# v2_1.net
KiCad netlist of a schematic drawn in EAGLE
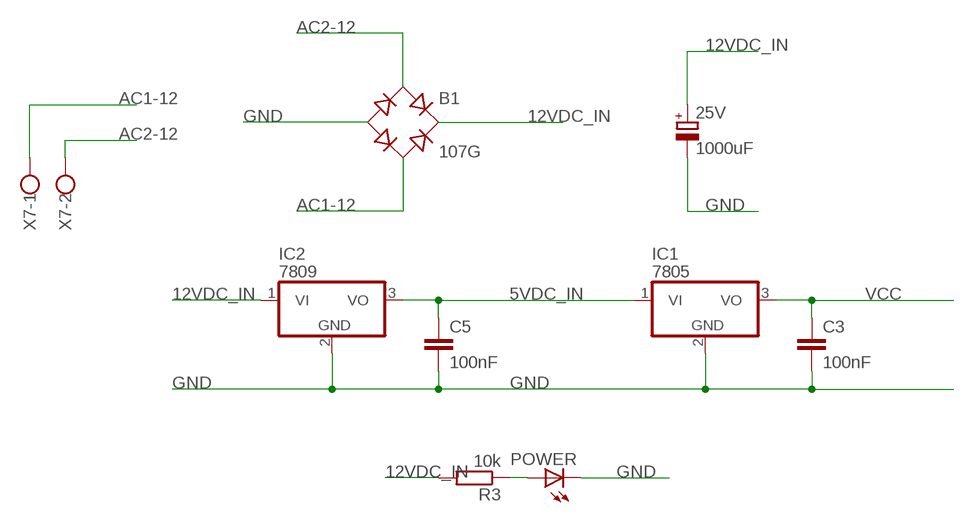
[diagram p0: schematic, sheet 1]
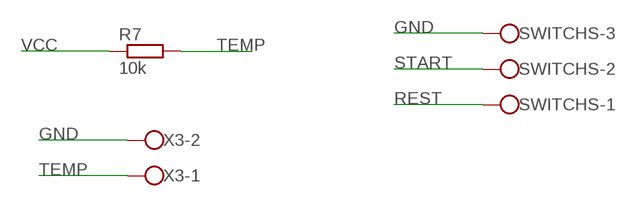
[diagram p1: schematic, sheet 2]
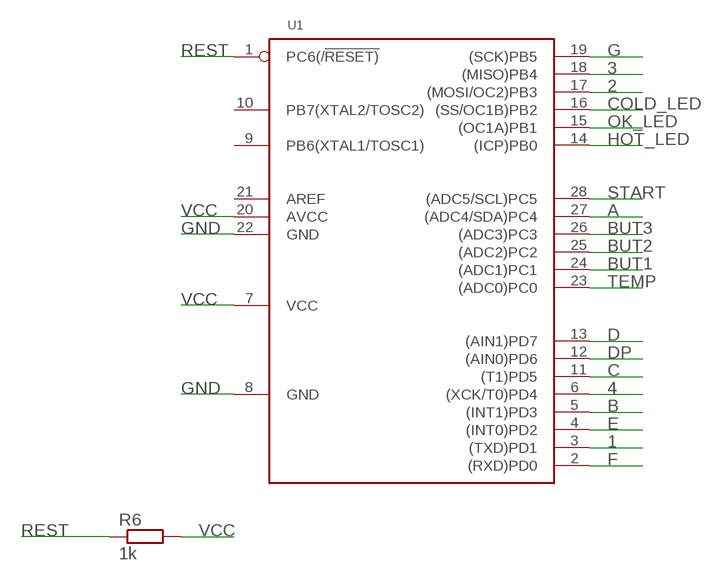
[diagram p2: schematic, sheet 3]
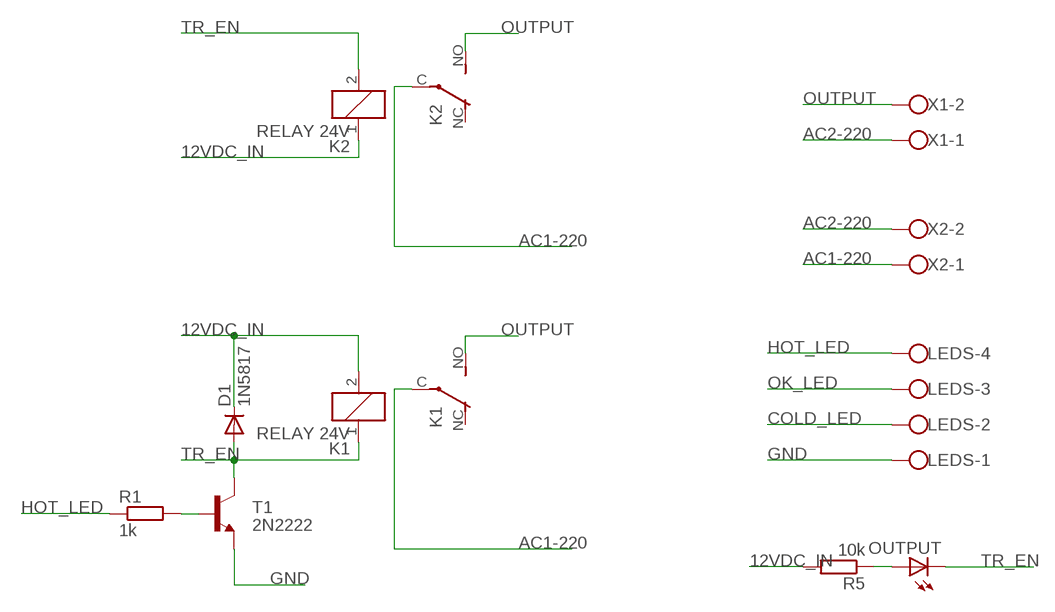
[diagram p3: schematic, sheet 4]

(export (version "E")
  (design (tool "Eeschema 10.0.6"))
  (components
    (comp (ref "25V")
      (value "1000uF")
      (footprint "eagle-import:E3,5-8")
      (libsource (lib "eagle-import") (part "CPOL-EUE3.5-8"))
    )
    (comp (ref "B1")
      (value "107G")
      (footprint "eagle-import:DB")
      (libsource (lib "eagle-import") (part "DB?GDB101"))
    )
    (comp (ref "C3")
      (value "100nF")
      (footprint "eagle-import:C050-025X075")
      (libsource (lib "eagle-import") (part "C-EU050-025X075"))
    )
    (comp (ref "C5")
      (value "100nF")
      (footprint "eagle-import:C050-025X075")
      (libsource (lib "eagle-import") (part "C-EU050-025X075"))
    )
    (comp (ref "IC1")
      (value "7805")
      (footprint "eagle-import:TO220V")
      (libsource (lib "eagle-import") (part "78TV12"))
    )
    (comp (ref "IC2")
      (value "7809")
      (footprint "eagle-import:TO220V")
      (libsource (lib "eagle-import") (part "78TV12"))
    )
    (comp (ref "POWER")
      (value "LED5MM")
      (footprint "eagle-import:LED5MM")
      (libsource (lib "eagle-import") (part "LED5MM"))
    )
    (comp (ref "R3")
      (value "10k")
      (footprint "eagle-import:0207_10")
      (libsource (lib "eagle-import") (part "R-EU_0207/10"))
    )
    (comp (ref "X7")
      (value "W237-102")
      (footprint "eagle-import:W237-102")
      (libsource (lib "eagle-import") (part "W237-102"))
    )
    (comp (ref "D1")
      (value "1N5817")
      (footprint "eagle-import:DO41-10")
      (libsource (lib "eagle-import") (part "1N4004"))
    )
    (comp (ref "K1")
      (value "RELAY 24V")
      (footprint "eagle-import:JS-M")
      (fields (field (name "MF") "FARNELL") (field (name "MPN") "JSM1-12V-5"))
      (libsource (lib "eagle-import") (part "JS-M1-12V-5"))
    )
    (comp (ref "K2")
      (value "RELAY 24V")
      (footprint "eagle-import:JS-M")
      (fields (field (name "MF") "FARNELL") (field (name "MPN") "JSM1-12V-5"))
      (libsource (lib "eagle-import") (part "JS-M1-12V-5"))
    )
    (comp (ref "LEDS")
      (value "W237-4")
      (footprint "eagle-import:W237-4")
      (libsource (lib "eagle-import") (part "W237-4"))
    )
    (comp (ref "OUTPUT")
      (value "LED5MM")
      (footprint "eagle-import:LED5MM")
      (libsource (lib "eagle-import") (part "LED5MM"))
    )
    (comp (ref "R1")
      (value "1k")
      (footprint "eagle-import:0207_10")
      (libsource (lib "eagle-import") (part "R-EU_0207/10"))
    )
    (comp (ref "R5")
      (value "10k")
      (footprint "eagle-import:0207_10")
      (libsource (lib "eagle-import") (part "R-EU_0207/10"))
    )
    (comp (ref "T1")
      (value "2N2222")
      (footprint "eagle-import:TO92-EBC-OVAL")
      (libsource (lib "eagle-import") (part "2N2222"))
    )
    (comp (ref "X1")
      (value "W237-102")
      (footprint "eagle-import:W237-102")
      (libsource (lib "eagle-import") (part "W237-102"))
    )
    (comp (ref "X2")
      (value "W237-102")
      (footprint "eagle-import:W237-102")
      (libsource (lib "eagle-import") (part "W237-102"))
    )
    (comp (ref "R6")
      (value "1k")
      (footprint "eagle-import:0207_10")
      (libsource (lib "eagle-import") (part "R-EU_0207/10"))
    )
    (comp (ref "U1")
      (value "MCU-ATMEGA328P-PU(DIP28)")
      (footprint "eagle-import:DIP28-2.54-34.7X7.62MM")
      (fields (field (name "MPN") "ATMEGA328P-PU"))
      (libsource (lib "eagle-import") (part "MCU-ATMEGA328P-PU(DIP28)"))
    )
    (comp (ref "R7")
      (value "10k")
      (footprint "eagle-import:0207_10")
      (libsource (lib "eagle-import") (part "R-EU_0207/10"))
    )
    (comp (ref "SWITCHS")
      (value "W237-103")
      (footprint "eagle-import:W237-103")
      (libsource (lib "eagle-import") (part "W237-103"))
    )
    (comp (ref "X3")
      (value "W237-102")
      (footprint "eagle-import:W237-102")
      (libsource (lib "eagle-import") (part "W237-102"))
    )
  )
  (nets
    (net (code "1") (name "1") (class "Default")
      (node (ref "U1") (pin "3") (pinfunction "(TXD)PD1_3") (pintype "bidirectional"))
    )
    (net (code "2") (name "2") (class "Default")
      (node (ref "U1") (pin "17") (pinfunction "(MOSI/OC2)PB3_17") (pintype "bidirectional"))
    )
    (net (code "3") (name "3") (class "Default")
      (node (ref "U1") (pin "18") (pinfunction "(MISO)PB4_18") (pintype "bidirectional"))
    )
    (net (code "4") (name "4") (class "Default")
      (node (ref "U1") (pin "6") (pinfunction "(XCK/T0)PD4_6") (pintype "bidirectional"))
    )
    (net (code "5") (name "5VDC_IN") (class "Default")
      (node (ref "C5") (pin "1") (pinfunction "1_1") (pintype "passive"))
      (node (ref "IC1") (pin "1") (pinfunction "VI_1") (pintype "input"))
      (node (ref "IC2") (pin "3") (pinfunction "VO_3") (pintype "passive"))
    )
    (net (code "6") (name "12VDC_IN") (class "Default")
      (node (ref "25V") (pin "+") (pinfunction "+_+") (pintype "passive"))
      (node (ref "B1") (pin "+") (pinfunction "+_+") (pintype "passive"))
      (node (ref "D1") (pin "C") (pinfunction "C_C") (pintype "passive"))
      (node (ref "IC2") (pin "1") (pinfunction "VI_1") (pintype "input"))
      (node (ref "K1") (pin "2") (pinfunction "2_2") (pintype "passive"))
      (node (ref "K2") (pin "1") (pinfunction "1_1") (pintype "passive"))
      (node (ref "R3") (pin "2") (pinfunction "2_2") (pintype "passive"))
      (node (ref "R5") (pin "2") (pinfunction "2_2") (pintype "passive"))
    )
    (net (code "7") (name "A") (class "Default")
      (node (ref "U1") (pin "27") (pinfunction "(ADC4/SDA)PC4_27") (pintype "bidirectional"))
    )
    (net (code "8") (name "AC1-12") (class "Default")
      (node (ref "B1") (pin "AC2") (pinfunction "AC2_AC2") (pintype "passive"))
      (node (ref "X7") (pin "1") (pinfunction "KL_1") (pintype "passive"))
    )
    (net (code "9") (name "AC1-220") (class "Default")
      (node (ref "K1") (pin "C") (pinfunction "P_C") (pintype "passive"))
      (node (ref "K2") (pin "C") (pinfunction "P_C") (pintype "passive"))
      (node (ref "X2") (pin "1") (pinfunction "KL_1") (pintype "passive"))
    )
    (net (code "10") (name "AC2-12") (class "Default")
      (node (ref "B1") (pin "AC1") (pinfunction "AC1_AC1") (pintype "passive"))
      (node (ref "X7") (pin "2") (pinfunction "KL_2") (pintype "passive"))
    )
    (net (code "11") (name "AC2-220") (class "Default")
      (node (ref "X1") (pin "1") (pinfunction "KL_1") (pintype "passive"))
      (node (ref "X2") (pin "2") (pinfunction "KL_2") (pintype "passive"))
    )
    (net (code "12") (name "B") (class "Default")
      (node (ref "U1") (pin "5") (pinfunction "(INT1)PD3_5") (pintype "bidirectional"))
    )
    (net (code "13") (name "BUT1") (class "Default")
      (node (ref "U1") (pin "24") (pinfunction "(ADC1)PC1_24") (pintype "bidirectional"))
    )
    (net (code "14") (name "BUT2") (class "Default")
      (node (ref "U1") (pin "25") (pinfunction "(ADC2)PC2_25") (pintype "bidirectional"))
    )
    (net (code "15") (name "BUT3") (class "Default")
      (node (ref "U1") (pin "26") (pinfunction "(ADC3)PC3_26") (pintype "bidirectional"))
    )
    (net (code "16") (name "C") (class "Default")
      (node (ref "U1") (pin "11") (pinfunction "(T1)PD5_11") (pintype "bidirectional"))
    )
    (net (code "17") (name "COLD_LED") (class "Default")
      (node (ref "LEDS") (pin "2") (pinfunction "KL_2") (pintype "passive"))
      (node (ref "U1") (pin "16") (pinfunction "(SS/OC1B)PB2_16") (pintype "bidirectional"))
    )
    (net (code "18") (name "D") (class "Default")
      (node (ref "U1") (pin "13") (pinfunction "(AIN1)PD7_13") (pintype "bidirectional"))
    )
    (net (code "19") (name "DP") (class "Default")
      (node (ref "U1") (pin "12") (pinfunction "(AIN0)PD6_12") (pintype "bidirectional"))
    )
    (net (code "20") (name "E") (class "Default")
      (node (ref "U1") (pin "4") (pinfunction "(INT0)PD2_4") (pintype "bidirectional"))
    )
    (net (code "21") (name "F") (class "Default")
      (node (ref "U1") (pin "2") (pinfunction "(RXD)PD0_2") (pintype "bidirectional"))
    )
    (net (code "22") (name "G") (class "Default")
      (node (ref "U1") (pin "19") (pinfunction "(SCK)PB5_19") (pintype "bidirectional"))
    )
    (net (code "23") (name "GND") (class "Default")
      (node (ref "25V") (pin "-") (pinfunction "-_-") (pintype "passive"))
      (node (ref "B1") (pin "-") (pinfunction "-_-") (pintype "passive"))
      (node (ref "C3") (pin "2") (pinfunction "2_2") (pintype "passive"))
      (node (ref "C5") (pin "2") (pinfunction "2_2") (pintype "passive"))
      (node (ref "IC1") (pin "2") (pinfunction "GND_2") (pintype "passive"))
      (node (ref "IC2") (pin "2") (pinfunction "GND_2") (pintype "passive"))
      (node (ref "LEDS") (pin "1") (pinfunction "KL_1") (pintype "passive"))
      (node (ref "POWER") (pin "K") (pinfunction "C_K") (pintype "passive"))
      (node (ref "SWITCHS") (pin "3") (pinfunction "KL_3") (pintype "passive"))
      (node (ref "T1") (pin "E") (pinfunction "E_E") (pintype "passive"))
      (node (ref "U1") (pin "22") (pinfunction "GND_22") (pintype "bidirectional"))
      (node (ref "U1") (pin "8") (pinfunction "GND_8") (pintype "bidirectional"))
      (node (ref "X3") (pin "2") (pinfunction "KL_2") (pintype "passive"))
    )
    (net (code "24") (name "HOT_LED") (class "Default")
      (node (ref "LEDS") (pin "4") (pinfunction "KL_4") (pintype "passive"))
      (node (ref "R1") (pin "1") (pinfunction "1_1") (pintype "passive"))
      (node (ref "U1") (pin "14") (pinfunction "(ICP)PB0_14") (pintype "bidirectional"))
    )
    (net (code "25") (name "Net-(OUTPUT-PadA)") (class "Default")
      (node (ref "OUTPUT") (pin "A") (pinfunction "A_A") (pintype "passive"))
      (node (ref "R5") (pin "1") (pinfunction "1_1") (pintype "passive"))
    )
    (net (code "26") (name "Net-(POWER-PadA)") (class "Default")
      (node (ref "POWER") (pin "A") (pinfunction "A_A") (pintype "passive"))
      (node (ref "R3") (pin "1") (pinfunction "1_1") (pintype "passive"))
    )
    (net (code "27") (name "Net-(R1-Pad2)") (class "Default")
      (node (ref "R1") (pin "2") (pinfunction "2_2") (pintype "passive"))
      (node (ref "T1") (pin "B") (pinfunction "B_B") (pintype "passive"))
    )
    (net (code "28") (name "OK_LED") (class "Default")
      (node (ref "LEDS") (pin "3") (pinfunction "KL_3") (pintype "passive"))
      (node (ref "U1") (pin "15") (pinfunction "(OC1A)PB1_15") (pintype "bidirectional"))
    )
    (net (code "29") (name "OUTPUT") (class "Default")
      (node (ref "K1") (pin "NO") (pinfunction "S_NO") (pintype "passive"))
      (node (ref "K2") (pin "NO") (pinfunction "S_NO") (pintype "passive"))
      (node (ref "X1") (pin "2") (pinfunction "KL_2") (pintype "passive"))
    )
    (net (code "30") (name "REST") (class "Default")
      (node (ref "R6") (pin "1") (pinfunction "1_1") (pintype "passive"))
      (node (ref "SWITCHS") (pin "1") (pinfunction "KL_1") (pintype "passive"))
      (node (ref "U1") (pin "1") (pinfunction "PC6(/~{RESET})_1") (pintype "bidirectional"))
    )
    (net (code "31") (name "START") (class "Default")
      (node (ref "SWITCHS") (pin "2") (pinfunction "KL_2") (pintype "passive"))
      (node (ref "U1") (pin "28") (pinfunction "(ADC5/SCL)PC5_28") (pintype "bidirectional"))
    )
    (net (code "32") (name "TEMP") (class "Default")
      (node (ref "R7") (pin "2") (pinfunction "2_2") (pintype "passive"))
      (node (ref "U1") (pin "23") (pinfunction "(ADC0)PC0_23") (pintype "bidirectional"))
      (node (ref "X3") (pin "1") (pinfunction "KL_1") (pintype "passive"))
    )
    (net (code "33") (name "TR_EN") (class "Default")
      (node (ref "D1") (pin "A") (pinfunction "A_A") (pintype "passive"))
      (node (ref "K1") (pin "1") (pinfunction "1_1") (pintype "passive"))
      (node (ref "K2") (pin "2") (pinfunction "2_2") (pintype "passive"))
      (node (ref "OUTPUT") (pin "K") (pinfunction "C_K") (pintype "passive"))
      (node (ref "T1") (pin "C") (pinfunction "C_C") (pintype "passive"))
    )
    (net (code "34") (name "VCC") (class "Default")
      (node (ref "C3") (pin "1") (pinfunction "1_1") (pintype "passive"))
      (node (ref "IC1") (pin "3") (pinfunction "VO_3") (pintype "passive"))
      (node (ref "R6") (pin "2") (pinfunction "2_2") (pintype "passive"))
      (node (ref "R7") (pin "1") (pinfunction "1_1") (pintype "passive"))
      (node (ref "U1") (pin "20") (pinfunction "AVCC_20") (pintype "bidirectional"))
      (node (ref "U1") (pin "7") (pinfunction "VCC_7") (pintype "bidirectional"))
    )
    (net (code "35") (name "unconnected-(K1B-O-PadNC)") (class "Default")
      (node (ref "K1") (pin "NC") (pinfunction "O_NC") (pintype "passive"))
    )
    (net (code "36") (name "unconnected-(K2B-O-PadNC)") (class "Default")
      (node (ref "K2") (pin "NC") (pinfunction "O_NC") (pintype "passive"))
    )
    (net (code "37") (name "unconnected-(U1-AREF-Pad21)") (class "Default")
      (node (ref "U1") (pin "21") (pinfunction "AREF_21") (pintype "bidirectional"))
    )
    (net (code "38") (name "unconnected-(U1-PB6(XTAL1{slash}TOSC1)-Pad9)") (class "Default")
      (node (ref "U1") (pin "9") (pinfunction "PB6(XTAL1/TOSC1)_9") (pintype "bidirectional"))
    )
    (net (code "39") (name "unconnected-(U1-PB7(XTAL2{slash}TOSC2)-Pad10)") (class "Default")
      (node (ref "U1") (pin "10") (pinfunction "PB7(XTAL2/TOSC2)_10") (pintype "bidirectional"))
    )
  )
)
